# Main.net
KiCad netlist of a schematic drawn in Altium Designer
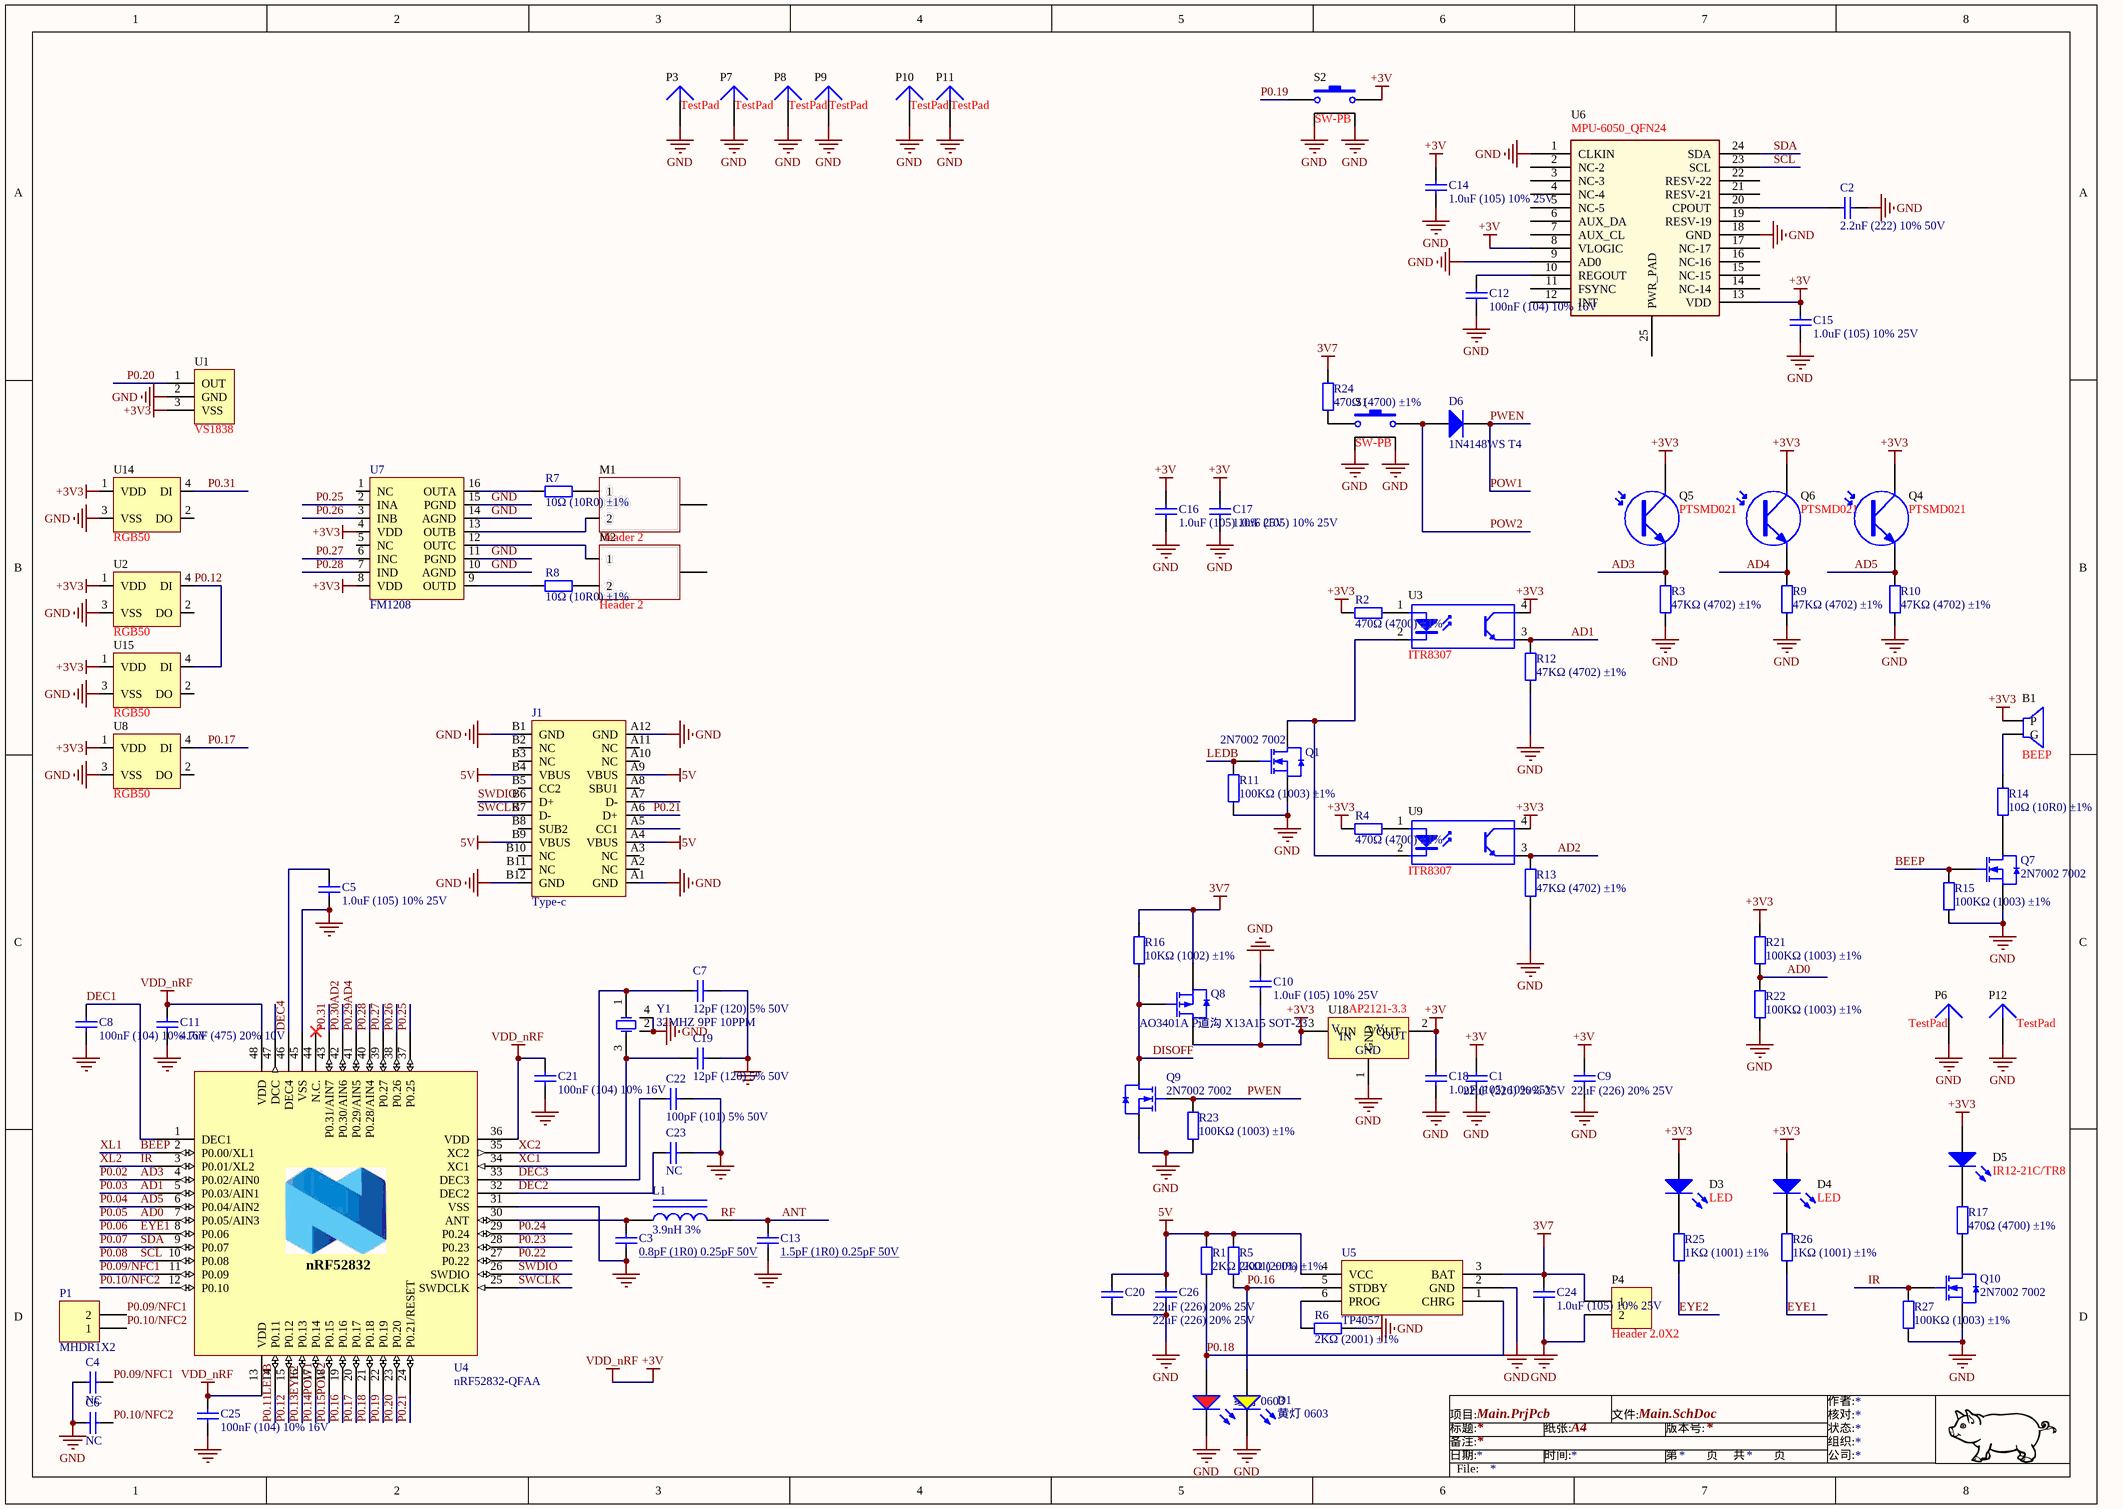
[diagram p0: Main.SchDoc]

(export (version "E")
  (design (tool "Eeschema 10.0.6"))
  (components
    (comp (ref "B1")
      (value "BEEP")
      (footprint "BEEP")
      (description "最小蜂鸣器6MM 6038 6035电磁式蜂鸣器 6*3.5 6*3.8MM 无源 交流")
      (libsource (lib "WARSHIP_SCH") (part "BEEP"))
    )
    (comp (ref "C1")
      (value "22uF (226) 20% 25V")
      (footprint "0805_C")
      (description "贴片电容")
      (libsource (lib "Miscellaneous Devices LC") (part "0805 22uF (226) 20% 25V"))
    )
    (comp (ref "C2")
      (value "2.2nF (222) 10% 50V")
      (footprint "0402_C")
      (description "贴片电容")
      (libsource (lib "Miscellaneous Devices LC") (part "0402 2.2nF (222) 10% 50V"))
    )
    (comp (ref "C3")
      (value "0.8pF (1R0) 0.25pF 50V")
      (footprint "0402_C")
      (description "贴片电容")
      (libsource (lib "Miscellaneous Devices LC") (part "0402 1pF (1R0) 0.25pF 50V"))
    )
    (comp (ref "C4")
      (value "NC")
      (footprint "0402_C")
      (description "贴片电容")
      (libsource (lib "LC") (part "0402 1nF (102) 10% 50V"))
    )
    (comp (ref "C5")
      (value "1.0uF (105) 10% 25V")
      (footprint "0402_C")
      (description "贴片电容")
      (libsource (lib "Miscellaneous Devices LC") (part "0402 1.0uF (105) 10% 25V"))
    )
    (comp (ref "C6")
      (value "NC")
      (footprint "0402_C")
      (description "贴片电容")
      (libsource (lib "LC") (part "0402 1nF (102) 10% 50V"))
    )
    (comp (ref "C7")
      (value "12pF (120) 5% 50V")
      (footprint "0402_C")
      (description "贴片电容")
      (libsource (lib "Miscellaneous Devices LC") (part "0402 12pF (120) 5% 50V"))
    )
    (comp (ref "C8")
      (value "100nF (104) 10% 16V")
      (footprint "0402_C")
      (description "贴片电容")
      (libsource (lib "Miscellaneous Devices LC") (part "0402 100nF (104) 10% 16V"))
    )
    (comp (ref "C9")
      (value "22uF (226) 20% 25V")
      (footprint "0805_C")
      (description "贴片电容")
      (libsource (lib "Miscellaneous Devices LC") (part "0805 22uF (226) 20% 25V"))
    )
    (comp (ref "C10")
      (value "1.0uF (105) 10% 25V")
      (footprint "0402_C")
      (description "贴片电容")
      (libsource (lib "Miscellaneous Devices LC") (part "0402 1.0uF (105) 10% 25V"))
    )
    (comp (ref "C11")
      (value "4.7uF (475) 20% 10V")
      (footprint "0402_C")
      (description "贴片电容")
      (libsource (lib "Miscellaneous Devices LC") (part "0402 4.7uF (475) 20% 10V"))
    )
    (comp (ref "C12")
      (value "100nF (104) 10% 16V")
      (footprint "0402_C")
      (description "贴片电容")
      (libsource (lib "Miscellaneous Devices LC") (part "0402 100nF (104) 10% 16V"))
    )
    (comp (ref "C13")
      (value "1.5pF (1R0) 0.25pF 50V")
      (footprint "0402_C")
      (description "贴片电容")
      (libsource (lib "Miscellaneous Devices LC") (part "0402 1pF (1R0) 0.25pF 50V"))
    )
    (comp (ref "C14")
      (value "1.0uF (105) 10% 25V")
      (footprint "0402_C")
      (description "贴片电容")
      (libsource (lib "Miscellaneous Devices LC") (part "0402 1.0uF (105) 10% 25V"))
    )
    (comp (ref "C15")
      (value "1.0uF (105) 10% 25V")
      (footprint "0402_C")
      (description "贴片电容")
      (libsource (lib "Miscellaneous Devices LC") (part "0402 1.0uF (105) 10% 25V"))
    )
    (comp (ref "C16")
      (value "1.0uF (105) 10% 25V")
      (footprint "0402_C")
      (description "贴片电容")
      (libsource (lib "Miscellaneous Devices LC") (part "0402 1.0uF (105) 10% 25V"))
    )
    (comp (ref "C17")
      (value "1.0uF (105) 10% 25V")
      (footprint "0402_C")
      (description "贴片电容")
      (libsource (lib "Miscellaneous Devices LC") (part "0402 1.0uF (105) 10% 25V"))
    )
    (comp (ref "C18")
      (value "1.0uF (105) 10% 25V")
      (footprint "0402_C")
      (description "贴片电容")
      (libsource (lib "Miscellaneous Devices LC") (part "0402 1.0uF (105) 10% 25V"))
    )
    (comp (ref "C19")
      (value "12pF (120) 5% 50V")
      (footprint "0402_C")
      (description "贴片电容")
      (libsource (lib "Miscellaneous Devices LC") (part "0402 12pF (120) 5% 50V"))
    )
    (comp (ref "C20")
      (value "22uF (226) 20% 25V")
      (footprint "0805_C")
      (description "贴片电容")
      (libsource (lib "Miscellaneous Devices LC") (part "0805 22uF (226) 20% 25V"))
    )
    (comp (ref "C21")
      (value "100nF (104) 10% 16V")
      (footprint "0402_C")
      (description "贴片电容")
      (libsource (lib "Miscellaneous Devices LC") (part "0402 100nF (104) 10% 16V"))
    )
    (comp (ref "C22")
      (value "100pF (101) 5% 50V")
      (footprint "0402_C")
      (description "贴片电容")
      (libsource (lib "Miscellaneous Devices LC") (part "0402 100pF (101) 5% 50V"))
    )
    (comp (ref "C23")
      (value "NC")
      (footprint "0402_C")
      (description "贴片电容")
      (libsource (lib "Miscellaneous Devices LC") (part "0402 100pF (101) 5% 50V"))
    )
    (comp (ref "C24")
      (value "1.0uF (105) 10% 25V")
      (footprint "0402_C")
      (description "贴片电容")
      (libsource (lib "Miscellaneous Devices LC") (part "0402 1.0uF (105) 10% 25V"))
    )
    (comp (ref "C25")
      (value "100nF (104) 10% 16V")
      (footprint "0402_C")
      (description "贴片电容")
      (libsource (lib "Miscellaneous Devices LC") (part "0402 100nF (104) 10% 16V"))
    )
    (comp (ref "C26")
      (value "22uF (226) 20% 25V")
      (footprint "0805_C")
      (description "贴片电容")
      (libsource (lib "Miscellaneous Devices LC") (part "0805 22uF (226) 20% 25V"))
    )
    (comp (ref "D1")
      (value "黄灯 0603")
      (footprint "0603_LED_S1")
      (description "发光二极管")
      (libsource (lib "Miscellaneous Devices LC") (part "0603 黄灯"))
    )
    (comp (ref "D2")
      (value "红灯 0603")
      (footprint "0603_LED_S1")
      (description "发光二极管")
      (libsource (lib "Miscellaneous Devices LC") (part "0603 红灯"))
    )
    (comp (ref "D3")
      (value "LED")
      (footprint "0802")
      (description "Typical RED, GREEN, YELLOW, AMBER GaAs LED")
      (fields (field (name "PUBLISHER") "Altium Limited"))
      (libsource (lib "Miscellaneous Devices") (part "LED0805"))
    )
    (comp (ref "D4")
      (value "LED")
      (footprint "0802")
      (description "Typical RED, GREEN, YELLOW, AMBER GaAs LED")
      (fields (field (name "PUBLISHER") "Altium Limited"))
      (libsource (lib "Miscellaneous Devices") (part "LED0805"))
    )
    (comp (ref "D5")
      (value "IR12-21C/TR8")
      (footprint "1206")
      (description "侧贴红外发射管")
      (fields (field (name "PUBLISHER") "Altium Limited"))
      (libsource (lib "Miscellaneous Devices") (part "LED0805"))
    )
    (comp (ref "D6")
      (value "1N4148WS T4")
      (footprint "SOD-323")
      (description "二极管")
      (libsource (lib "Miscellaneous Devices LC") (part "SOD-323 1N4148WS T4"))
    )
    (comp (ref "J1") (value "Type-c") (footprint "Type-c") (libsource (lib "Main") (part "Type-c")))
    (comp (ref "L1")
      (value "3.9nH 3%")
      (footprint "0402_L")
      (description "贴片电感")
      (libsource (lib "Miscellaneous Devices LC") (part "0402 3.9nH 3%"))
    )
    (comp (ref "M1")
      (value "Header 2")
      (footprint "PAD2")
      (description "Header, 2-Pin")
      (fields (field (name "PUBLISHER") "Altium Limited"))
      (libsource (lib "甲壳虫Geek-InSect_1") (part "Header 2"))
    )
    (comp (ref "M2")
      (value "Header 2")
      (footprint "PAD2")
      (description "Header, 2-Pin")
      (fields (field (name "PUBLISHER") "Altium Limited"))
      (libsource (lib "甲壳虫Geek-InSect_1") (part "Header 2"))
    )
    (comp (ref "P1")
      (value "MHDR1X2")
      (footprint "MHDR1X2")
      (description "Header, 2-Pin")
      (fields (field (name "PUBLISHER") "Altium Limited"))
      (libsource (lib "Miscellaneous Connectors") (part "MHDR1X2"))
    )
    (comp (ref "P3")
      (value "TestPad")
      (footprint "MOTO")
      (description "Plug")
      (fields (field (name "PUBLISHER") "Altium Limited"))
      (libsource (lib "Miscellaneous Connectors") (part "Plug"))
    )
    (comp (ref "P4")
      (value "Header 2.0X2")
      (footprint "Head2.0")
      (description "2.0dip连接器")
      (fields (field (name "PUBLISHER") "Altium Limited"))
      (libsource (lib "Miscellaneous Connectors") (part "Header 2"))
    )
    (comp (ref "P6")
      (value "TestPad")
      (footprint "PAD")
      (description "Plug")
      (fields (field (name "PUBLISHER") "Altium Limited"))
      (libsource (lib "Miscellaneous Connectors") (part "Plug"))
    )
    (comp (ref "P7")
      (value "TestPad")
      (footprint "MOTO")
      (description "Plug")
      (fields (field (name "PUBLISHER") "Altium Limited"))
      (libsource (lib "Miscellaneous Connectors") (part "Plug"))
    )
    (comp (ref "P8")
      (value "TestPad")
      (footprint "PAD")
      (description "Plug")
      (fields (field (name "PUBLISHER") "Altium Limited"))
      (libsource (lib "Miscellaneous Connectors") (part "Plug"))
    )
    (comp (ref "P9")
      (value "TestPad")
      (footprint "PAD")
      (description "Plug")
      (fields (field (name "PUBLISHER") "Altium Limited"))
      (libsource (lib "Miscellaneous Connectors") (part "Plug"))
    )
    (comp (ref "P10")
      (value "TestPad")
      (footprint "PAD")
      (description "Plug")
      (fields (field (name "PUBLISHER") "Altium Limited"))
      (libsource (lib "Miscellaneous Connectors") (part "Plug"))
    )
    (comp (ref "P11")
      (value "TestPad")
      (footprint "PAD")
      (description "Plug")
      (fields (field (name "PUBLISHER") "Altium Limited"))
      (libsource (lib "Miscellaneous Connectors") (part "Plug"))
    )
    (comp (ref "P12")
      (value "TestPad")
      (footprint "PAD")
      (description "Plug")
      (fields (field (name "PUBLISHER") "Altium Limited"))
      (libsource (lib "Miscellaneous Connectors") (part "Plug"))
    )
    (comp (ref "Q1")
      (value "2N7002 7002")
      (footprint "SOT-23")
      (description "MOS(场效应管)")
      (libsource (lib "Miscellaneous Devices LC") (part "2N7002 7002"))
    )
    (comp (ref "Q4")
      (value "PTSMD021")
      (footprint "EYE")
      (description "光线传感器")
      (fields (field (name "PUBLISHER") "Altium Limited"))
      (libsource (lib "Miscellaneous Devices") (part "Photo NPN"))
    )
    (comp (ref "Q5")
      (value "PTSMD021")
      (footprint "EYE")
      (description "光线传感器")
      (fields (field (name "PUBLISHER") "Altium Limited"))
      (libsource (lib "Miscellaneous Devices") (part "Photo NPN"))
    )
    (comp (ref "Q6")
      (value "PTSMD021")
      (footprint "EYE")
      (description "光线传感器")
      (fields (field (name "PUBLISHER") "Altium Limited"))
      (libsource (lib "Miscellaneous Devices") (part "Photo NPN"))
    )
    (comp (ref "Q7")
      (value "2N7002 7002")
      (footprint "SOT-23")
      (description "MOS(场效应管)")
      (libsource (lib "Miscellaneous Devices LC") (part "2N7002 7002"))
    )
    (comp (ref "Q8")
      (value "AO3401A P道沟 X13A15 SOT-23")
      (footprint "SOT-23-3L")
      (description "MOS(场效应管)")
      (libsource (lib "Miscellaneous Devices LC") (part "AO3401A P道沟 X13A15 SOT-23"))
    )
    (comp (ref "Q9")
      (value "2N7002 7002")
      (footprint "SOT-23")
      (description "MOS(场效应管)")
      (libsource (lib "Miscellaneous Devices LC") (part "2N7002 7002"))
    )
    (comp (ref "Q10")
      (value "2N7002 7002")
      (footprint "SOT-23")
      (description "MOS(场效应管)")
      (libsource (lib "Miscellaneous Devices LC") (part "2N7002 7002"))
    )
    (comp (ref "R1")
      (value "2KΩ (2001) ±1%")
      (footprint "0402_R")
      (description "贴片电阻")
      (libsource (lib "Miscellaneous Devices LC") (part "0402 2KΩ (2001) 1%"))
    )
    (comp (ref "R2")
      (value "470Ω (4700) ±1%")
      (footprint "0402_R")
      (description "贴片电阻")
      (libsource (lib "Miscellaneous Devices LC") (part "0402 470Ω (4700) 1%"))
    )
    (comp (ref "R3")
      (value "47KΩ (4702) ±1%")
      (footprint "0402_R")
      (description "贴片电阻")
      (libsource (lib "Miscellaneous Devices LC") (part "0402 47KΩ (4702) 1%"))
    )
    (comp (ref "R4")
      (value "470Ω (4700) ±1%")
      (footprint "0402_R")
      (description "贴片电阻")
      (libsource (lib "Miscellaneous Devices LC") (part "0402 470Ω (4700) 1%"))
    )
    (comp (ref "R5")
      (value "2KΩ (2001) ±1%")
      (footprint "0402_R")
      (description "贴片电阻")
      (libsource (lib "Miscellaneous Devices LC") (part "0402 2KΩ (2001) 1%"))
    )
    (comp (ref "R6")
      (value "2KΩ (2001) ±1%")
      (footprint "0402_R")
      (description "贴片电阻")
      (libsource (lib "") (part "0402 2KΩ (2001) 1%_1"))
    )
    (comp (ref "R7")
      (value "10Ω (10R0) ±1%")
      (footprint "0603_R")
      (description "贴片电阻")
      (libsource (lib "Miscellaneous Devices LC") (part "0603 10Ω (10R0) 1%"))
    )
    (comp (ref "R8")
      (value "10Ω (10R0) ±1%")
      (footprint "0603_R")
      (description "贴片电阻")
      (libsource (lib "Miscellaneous Devices LC") (part "0603 10Ω (10R0) 1%"))
    )
    (comp (ref "R9")
      (value "47KΩ (4702) ±1%")
      (footprint "0402_R")
      (description "贴片电阻")
      (libsource (lib "Miscellaneous Devices LC") (part "0402 47KΩ (4702) 1%"))
    )
    (comp (ref "R10")
      (value "47KΩ (4702) ±1%")
      (footprint "0402_R")
      (description "贴片电阻")
      (libsource (lib "Miscellaneous Devices LC") (part "0402 47KΩ (4702) 1%"))
    )
    (comp (ref "R11")
      (value "100KΩ (1003) ±1%")
      (footprint "0402_R")
      (description "贴片电阻")
      (libsource (lib "Miscellaneous Devices LC") (part "0402 100KΩ (1003) 1%"))
    )
    (comp (ref "R12")
      (value "47KΩ (4702) ±1%")
      (footprint "0402_R")
      (description "贴片电阻")
      (libsource (lib "Miscellaneous Devices LC") (part "0402 47KΩ (4702) 1%"))
    )
    (comp (ref "R13")
      (value "47KΩ (4702) ±1%")
      (footprint "0402_R")
      (description "贴片电阻")
      (libsource (lib "Miscellaneous Devices LC") (part "0402 47KΩ (4702) 1%"))
    )
    (comp (ref "R14")
      (value "10Ω (10R0) ±1%")
      (footprint "0402_R")
      (description "贴片电阻")
      (libsource (lib "Miscellaneous Devices LC") (part "0402 10Ω (10R0) 1%"))
    )
    (comp (ref "R15")
      (value "100KΩ (1003) ±1%")
      (footprint "0402_R")
      (description "贴片电阻")
      (libsource (lib "Miscellaneous Devices LC") (part "0402 100KΩ (1003) 1%"))
    )
    (comp (ref "R16")
      (value "10KΩ (1002) ±1%")
      (footprint "0402_R")
      (description "贴片电阻")
      (libsource (lib "Miscellaneous Devices LC") (part "0402 10KΩ (1002) 1%"))
    )
    (comp (ref "R17")
      (value "470Ω (4700) ±1%")
      (footprint "0402_R")
      (description "贴片电阻")
      (libsource (lib "") (part "0402 470Ω (4700) 1%_1"))
    )
    (comp (ref "R21")
      (value "100KΩ (1003) ±1%")
      (footprint "0402_R")
      (description "贴片电阻")
      (libsource (lib "Miscellaneous Devices LC") (part "0402 100KΩ (1003) 1%"))
    )
    (comp (ref "R22")
      (value "100KΩ (1003) ±1%")
      (footprint "0402_R")
      (description "贴片电阻")
      (libsource (lib "Miscellaneous Devices LC") (part "0402 100KΩ (1003) 1%"))
    )
    (comp (ref "R23")
      (value "100KΩ (1003) ±1%")
      (footprint "0402_R")
      (description "贴片电阻")
      (libsource (lib "Miscellaneous Devices LC") (part "0402 100KΩ (1003) 1%"))
    )
    (comp (ref "R24")
      (value "470Ω (4700) ±1%")
      (footprint "0402_R")
      (description "贴片电阻")
      (libsource (lib "") (part "0402 470Ω (4700) 1%_1"))
    )
    (comp (ref "R25")
      (value "1KΩ (1001) ±1%")
      (footprint "0402_R")
      (description "贴片电阻")
      (libsource (lib "Miscellaneous Devices LC") (part "0402 1KΩ (1001) 1%"))
    )
    (comp (ref "R26")
      (value "1KΩ (1001) ±1%")
      (footprint "0402_R")
      (description "贴片电阻")
      (libsource (lib "Miscellaneous Devices LC") (part "0402 1KΩ (1001) 1%"))
    )
    (comp (ref "R27")
      (value "100KΩ (1003) ±1%")
      (footprint "0402_R")
      (description "贴片电阻")
      (libsource (lib "Miscellaneous Devices LC") (part "0402 100KΩ (1003) 1%"))
    )
    (comp (ref "S1")
      (value "SW-PB")
      (footprint "BUTTON")
      (description "3x6x3.5H 3*6*3.5贴片 侧位 按钮")
      (fields (field (name "PUBLISHER") "Altium Limited"))
      (libsource (lib "甲壳虫Geek-InSect_1") (part "SW-PB"))
    )
    (comp (ref "S2")
      (value "SW-PB")
      (footprint "BUTTON")
      (description "3x6x3.5H 3*6*3.5贴片 侧位 按钮")
      (fields (field (name "PUBLISHER") "Altium Limited"))
      (libsource (lib "甲壳虫Geek-InSect_1") (part "SW-PB"))
    )
    (comp (ref "U1")
      (value "VS1838")
      (footprint "IR38")
      (description "1838 接收头 VS1838 VS1838B")
      (libsource (lib "甲壳虫Geek-InSect_1") (part "RF"))
    )
    (comp (ref "U2")
      (value "RGB50")
      (footprint "HV-EYE - duplicate")
      (description "全彩REG灯珠PCB附件")
      (libsource (lib "甲壳虫Geek-InSect") (part "RGB50"))
    )
    (comp (ref "U3")
      (value "ITR8307")
      (footprint "ITR8307")
      (description "反射式光学传感器")
      (fields (field (name "PUBLISHER") "Altium Limited"))
      (libsource (lib "甲壳虫Geek-InSect") (part "Optoisolator1"))
    )
    (comp (ref "U4")
      (value "nRF52832-QFAA")
      (footprint "QFN40P600X600X90-48N")
      (description "Multi-protocol Bluetooth Low Energy and 2.4GHz proprietary system-on-chip")
      (fields
        (field (name "MANUFACTURER") "Nordic Semiconductor")
        (field (name "PUBLISHER") "Nordic Semiconductor")
      )
      (libsource (lib "Nordic Active DB") (part "nRF52832_QFAA"))
    )
    (comp (ref "U5")
      (value "TP4057")
      (footprint "SOT23-6_N")
      (description "电池电源管理")
      (libsource (lib "Miscellaneous Devices LC") (part "TP4057"))
    )
    (comp (ref "U6")
      (value "MPU-6050_QFN24")
      (footprint "qfn24")
      (description "三轴陀螺仪加速度")
      (libsource (lib "*") (part "MPU06050_QFN24"))
    )
    (comp (ref "U7") (value "FM1208") (footprint "SO-16_L") (libsource (lib "Main") (part "FM1208S")))
    (comp (ref "U8")
      (value "RGB50")
      (footprint "WS2812")
      (description "WS2812全彩RGB灯珠")
      (libsource (lib "甲壳虫Geek-InSect") (part "RGB50"))
    )
    (comp (ref "U9")
      (value "ITR8307")
      (footprint "ITR8307")
      (description "反射式光学传感器")
      (fields (field (name "PUBLISHER") "Altium Limited"))
      (libsource (lib "甲壳虫Geek-InSect") (part "Optoisolator1"))
    )
    (comp (ref "U14")
      (value "RGB50")
      (footprint "WS2812")
      (description "WS2812全彩RGB灯珠")
      (libsource (lib "甲壳虫Geek-InSect") (part "RGB50"))
    )
    (comp (ref "U15")
      (value "RGB50")
      (footprint "HV-EYE - duplicate")
      (description "全彩REG灯珠PCB附件")
      (libsource (lib "甲壳虫Geek-InSect") (part "RGB50"))
    )
    (comp (ref "U18")
      (value "AP2121-3.3")
      (footprint "SOT-23")
      (description "3V LDO")
      (libsource (lib "wllibs") (part "AP2121-3"))
    )
    (comp (ref "Y1")
      (value "32MHZ 9PF 10PPM")
      (footprint "SMD-3225_4P")
      (description "贴片晶振")
      (libsource (lib "MiniCar") (part "SMD-3225_4P  16MHZ 9PF 10PPM"))
    )
  )
  (nets
    (net (code "1") (name "+3V") (class "Default")
      (node (ref "C1") (pin "2") (pinfunction "2_2") (pintype "passive"))
      (node (ref "C11") (pin "2") (pinfunction "2_2") (pintype "passive"))
      (node (ref "C14") (pin "2") (pinfunction "2_2") (pintype "passive"))
      (node (ref "C15") (pin "2") (pinfunction "2_2") (pintype "passive"))
      (node (ref "C16") (pin "2") (pinfunction "2_2") (pintype "passive"))
      (node (ref "C17") (pin "2") (pinfunction "2_2") (pintype "passive"))
      (node (ref "C18") (pin "2") (pinfunction "2_2") (pintype "passive"))
      (node (ref "C21") (pin "2") (pinfunction "2_2") (pintype "passive"))
      (node (ref "C25") (pin "2") (pinfunction "2_2") (pintype "passive"))
      (node (ref "C9") (pin "2") (pinfunction "2_2") (pintype "passive"))
      (node (ref "S2") (pin "1") (pinfunction "1_1") (pintype "passive"))
      (node (ref "U18") (pin "2") (pinfunction "VOUT_2") (pintype "passive"))
      (node (ref "U4") (pin "13") (pinfunction "VDD_13") (pintype "power_in"))
      (node (ref "U4") (pin "36") (pinfunction "VDD_36") (pintype "power_in"))
      (node (ref "U4") (pin "48") (pinfunction "VDD_48") (pintype "power_in"))
      (node (ref "U6") (pin "13") (pinfunction "VDD_13") (pintype "passive"))
      (node (ref "U6") (pin "8") (pinfunction "VLOGIC_8") (pintype "passive"))
    )
    (net (code "2") (name "+3V3") (class "Default")
      (node (ref "B1") (pin "1") (pinfunction "P_1") (pintype "passive"))
      (node (ref "C10") (pin "1") (pinfunction "1_1") (pintype "passive"))
      (node (ref "D3") (pin "1") (pinfunction "A_1") (pintype "passive"))
      (node (ref "D4") (pin "1") (pinfunction "A_1") (pintype "passive"))
      (node (ref "D5") (pin "1") (pinfunction "A_1") (pintype "passive"))
      (node (ref "Q4") (pin "1") (pinfunction "C_1") (pintype "passive"))
      (node (ref "Q5") (pin "1") (pinfunction "C_1") (pintype "passive"))
      (node (ref "Q6") (pin "1") (pinfunction "C_1") (pintype "passive"))
      (node (ref "Q8") (pin "3") (pinfunction "D_3") (pintype "passive"))
      (node (ref "R2") (pin "1") (pinfunction "1_1") (pintype "passive"))
      (node (ref "R21") (pin "2") (pinfunction "2_2") (pintype "passive"))
      (node (ref "R4") (pin "1") (pinfunction "1_1") (pintype "passive"))
      (node (ref "U1") (pin "3") (pinfunction "VSS_3") (pintype "passive"))
      (node (ref "U14") (pin "1") (pinfunction "VDD_1") (pintype "passive"))
      (node (ref "U15") (pin "1") (pinfunction "VDD_1") (pintype "passive"))
      (node (ref "U18") (pin "3") (pinfunction "VIN_3") (pintype "passive"))
      (node (ref "U2") (pin "1") (pinfunction "VDD_1") (pintype "passive"))
      (node (ref "U3") (pin "4") (pinfunction "C_4") (pintype "passive"))
      (node (ref "U7") (pin "4") (pinfunction "VDD_4") (pintype "passive"))
      (node (ref "U7") (pin "8") (pinfunction "VDD_8") (pintype "passive"))
      (node (ref "U8") (pin "1") (pinfunction "VDD_1") (pintype "passive"))
      (node (ref "U9") (pin "4") (pinfunction "C_4") (pintype "passive"))
    )
    (net (code "3") (name "/AD0") (class "Default")
      (node (ref "R21") (pin "1") (pinfunction "1_1") (pintype "passive"))
      (node (ref "R22") (pin "2") (pinfunction "2_2") (pintype "passive"))
      (node (ref "U4") (pin "7") (pinfunction "P0.05/AIN3_7") (pintype "bidirectional"))
    )
    (net (code "4") (name "/AD1") (class "Default")
      (node (ref "R12") (pin "2") (pinfunction "2_2") (pintype "passive"))
      (node (ref "U3") (pin "3") (pinfunction "E_3") (pintype "passive"))
      (node (ref "U4") (pin "5") (pinfunction "P0.03/AIN1_5") (pintype "bidirectional"))
    )
    (net (code "5") (name "/AD2") (class "Default")
      (node (ref "R13") (pin "2") (pinfunction "2_2") (pintype "passive"))
      (node (ref "U4") (pin "42") (pinfunction "P0.30/AIN6_42") (pintype "bidirectional"))
      (node (ref "U9") (pin "3") (pinfunction "E_3") (pintype "passive"))
    )
    (net (code "6") (name "/AD3") (class "Default")
      (node (ref "Q5") (pin "2") (pinfunction "E_2") (pintype "passive"))
      (node (ref "R3") (pin "2") (pinfunction "2_2") (pintype "passive"))
      (node (ref "U4") (pin "4") (pinfunction "P0.02/AIN0_4") (pintype "bidirectional"))
    )
    (net (code "7") (name "/AD4") (class "Default")
      (node (ref "Q6") (pin "2") (pinfunction "E_2") (pintype "passive"))
      (node (ref "R9") (pin "2") (pinfunction "2_2") (pintype "passive"))
      (node (ref "U4") (pin "41") (pinfunction "P0.29/AIN5_41") (pintype "bidirectional"))
    )
    (net (code "8") (name "/AD5") (class "Default")
      (node (ref "Q4") (pin "2") (pinfunction "E_2") (pintype "passive"))
      (node (ref "R10") (pin "2") (pinfunction "2_2") (pintype "passive"))
      (node (ref "U4") (pin "6") (pinfunction "P0.04/AIN2_6") (pintype "bidirectional"))
    )
    (net (code "9") (name "/ANT") (class "Default")
      (node (ref "C13") (pin "2") (pinfunction "2_2") (pintype "passive"))
      (node (ref "L1") (pin "2") (pinfunction "2_2") (pintype "passive"))
    )
    (net (code "10") (name "/BEEP") (class "Default")
      (node (ref "Q7") (pin "1") (pinfunction "G_1") (pintype "passive"))
      (node (ref "R15") (pin "2") (pinfunction "2_2") (pintype "passive"))
      (node (ref "U4") (pin "2") (pinfunction "P0.00/XL1_2") (pintype "bidirectional"))
    )
    (net (code "11") (name "/DEC1") (class "Default")
      (node (ref "C8") (pin "2") (pinfunction "2_2") (pintype "passive"))
      (node (ref "U4") (pin "1") (pinfunction "DEC1_1") (pintype "power_in"))
    )
    (net (code "12") (name "/DEC2") (class "Default")
      (node (ref "C23") (pin "1") (pinfunction "1_1") (pintype "passive"))
      (node (ref "U4") (pin "32") (pinfunction "DEC2_32") (pintype "power_in"))
    )
    (net (code "13") (name "/DEC3") (class "Default")
      (node (ref "C22") (pin "1") (pinfunction "1_1") (pintype "passive"))
      (node (ref "U4") (pin "33") (pinfunction "DEC3_33") (pintype "power_in"))
    )
    (net (code "14") (name "/DEC4") (class "Default")
      (node (ref "C5") (pin "2") (pinfunction "2_2") (pintype "passive"))
      (node (ref "U4") (pin "46") (pinfunction "DEC4_46") (pintype "power_in"))
    )
    (net (code "15") (name "/DISOFF") (class "Default")
      (node (ref "Q8") (pin "1") (pinfunction "G_1") (pintype "passive"))
      (node (ref "Q9") (pin "3") (pinfunction "D_3") (pintype "passive"))
      (node (ref "R16") (pin "1") (pinfunction "1_1") (pintype "passive"))
    )
    (net (code "16") (name "/EYE1") (class "Default")
      (node (ref "R26") (pin "1") (pinfunction "1_1") (pintype "passive"))
      (node (ref "U4") (pin "8") (pinfunction "P0.06_8") (pintype "bidirectional"))
    )
    (net (code "17") (name "/EYE2") (class "Default")
      (node (ref "R25") (pin "1") (pinfunction "1_1") (pintype "passive"))
      (node (ref "U4") (pin "16") (pinfunction "P0.13_16") (pintype "bidirectional"))
    )
    (net (code "18") (name "/IR") (class "Default")
      (node (ref "Q10") (pin "1") (pinfunction "G_1") (pintype "passive"))
      (node (ref "R27") (pin "2") (pinfunction "2_2") (pintype "passive"))
      (node (ref "U4") (pin "3") (pinfunction "P0.01/XL2_3") (pintype "bidirectional"))
    )
    (net (code "19") (name "/LEDB") (class "Default")
      (node (ref "Q1") (pin "1") (pinfunction "G_1") (pintype "passive"))
      (node (ref "R11") (pin "2") (pinfunction "2_2") (pintype "passive"))
      (node (ref "U4") (pin "14") (pinfunction "P0.11_14") (pintype "bidirectional"))
    )
    (net (code "20") (name "/P0.07") (class "Default")
      (node (ref "U4") (pin "9") (pinfunction "P0.07_9") (pintype "bidirectional"))
      (node (ref "U6") (pin "24") (pinfunction "SDA_24") (pintype "passive"))
    )
    (net (code "21") (name "/P0.08") (class "Default")
      (node (ref "U4") (pin "10") (pinfunction "P0.08_10") (pintype "bidirectional"))
      (node (ref "U6") (pin "23") (pinfunction "SCL_23") (pintype "passive"))
    )
    (net (code "22") (name "/P0.09{slash}NFC1") (class "Default")
      (node (ref "C4") (pin "1") (pinfunction "1_1") (pintype "passive"))
      (node (ref "P1") (pin "2") (pinfunction "2_2") (pintype "passive"))
      (node (ref "U4") (pin "11") (pinfunction "P0.09_11") (pintype "bidirectional"))
    )
    (net (code "23") (name "/P0.10{slash}NFC2") (class "Default")
      (node (ref "C6") (pin "2") (pinfunction "2_2") (pintype "passive"))
      (node (ref "P1") (pin "1") (pinfunction "1_1") (pintype "passive"))
      (node (ref "U4") (pin "12") (pinfunction "P0.10_12") (pintype "bidirectional"))
    )
    (net (code "24") (name "/P0.12") (class "Default")
      (node (ref "U15") (pin "4") (pinfunction "DI_4") (pintype "passive"))
      (node (ref "U2") (pin "4") (pinfunction "DI_4") (pintype "passive"))
      (node (ref "U4") (pin "15") (pinfunction "P0.12_15") (pintype "bidirectional"))
    )
    (net (code "25") (name "/P0.14") (class "Default")
      (node (ref "D6") (pin "2") (pinfunction "K_2") (pintype "passive"))
      (node (ref "Q9") (pin "1") (pinfunction "G_1") (pintype "passive"))
      (node (ref "R23") (pin "2") (pinfunction "2_2") (pintype "passive"))
      (node (ref "U4") (pin "17") (pinfunction "P0.14_17") (pintype "bidirectional"))
    )
    (net (code "26") (name "/P0.15") (class "Default")
      (node (ref "D6") (pin "1") (pinfunction "A_1") (pintype "passive"))
      (node (ref "S1") (pin "2") (pinfunction "2_2") (pintype "passive"))
      (node (ref "U4") (pin "18") (pinfunction "P0.15_18") (pintype "bidirectional"))
    )
    (net (code "27") (name "/P0.16") (class "Default")
      (node (ref "D1") (pin "A") (pinfunction "A_A") (pintype "passive"))
      (node (ref "R5") (pin "1") (pinfunction "1_1") (pintype "passive"))
      (node (ref "U4") (pin "19") (pinfunction "P0.16_19") (pintype "bidirectional"))
      (node (ref "U5") (pin "5") (pinfunction "STDBY_5") (pintype "passive"))
    )
    (net (code "28") (name "/P0.17") (class "Default")
      (node (ref "U4") (pin "20") (pinfunction "P0.17_20") (pintype "bidirectional"))
      (node (ref "U8") (pin "4") (pinfunction "DI_4") (pintype "passive"))
    )
    (net (code "29") (name "/P0.18") (class "Default")
      (node (ref "D2") (pin "A") (pinfunction "A_A") (pintype "passive"))
      (node (ref "R1") (pin "1") (pinfunction "1_1") (pintype "passive"))
      (node (ref "U4") (pin "21") (pinfunction "P0.18_21") (pintype "bidirectional"))
      (node (ref "U5") (pin "1") (pinfunction "CHRG_1") (pintype "passive"))
    )
    (net (code "30") (name "/P0.19") (class "Default")
      (node (ref "S2") (pin "2") (pinfunction "2_2") (pintype "passive"))
      (node (ref "U4") (pin "22") (pinfunction "P0.19_22") (pintype "bidirectional"))
    )
    (net (code "31") (name "/P0.20") (class "Default")
      (node (ref "U1") (pin "1") (pinfunction "OUT_1") (pintype "passive"))
      (node (ref "U4") (pin "23") (pinfunction "P0.20_23") (pintype "bidirectional"))
    )
    (net (code "32") (name "/P0.21") (class "Default")
      (node (ref "J1") (pin "A6") (pinfunction "D+_A6") (pintype "passive"))
      (node (ref "U4") (pin "24") (pinfunction "P0.21/RESET_24") (pintype "bidirectional"))
    )
    (net (code "33") (name "/P0.22") (class "Default")
      (node (ref "U4") (pin "27") (pinfunction "P0.22_27") (pintype "bidirectional"))
    )
    (net (code "34") (name "/P0.23") (class "Default")
      (node (ref "U4") (pin "28") (pinfunction "P0.23_28") (pintype "bidirectional"))
    )
    (net (code "35") (name "/P0.24") (class "Default")
      (node (ref "U4") (pin "29") (pinfunction "P0.24_29") (pintype "bidirectional"))
    )
    (net (code "36") (name "/P0.25") (class "Default")
      (node (ref "U4") (pin "37") (pinfunction "P0.25_37") (pintype "bidirectional"))
      (node (ref "U7") (pin "2") (pinfunction "INA_2") (pintype "passive"))
    )
    (net (code "37") (name "/P0.26") (class "Default")
      (node (ref "U4") (pin "38") (pinfunction "P0.26_38") (pintype "bidirectional"))
      (node (ref "U7") (pin "3") (pinfunction "INB_3") (pintype "passive"))
    )
    (net (code "38") (name "/P0.27") (class "Default")
      (node (ref "U4") (pin "39") (pinfunction "P0.27_39") (pintype "bidirectional"))
      (node (ref "U7") (pin "6") (pinfunction "INC_6") (pintype "passive"))
    )
    (net (code "39") (name "/P0.28") (class "Default")
      (node (ref "U4") (pin "40") (pinfunction "P0.28/AIN4_40") (pintype "bidirectional"))
      (node (ref "U7") (pin "7") (pinfunction "IND_7") (pintype "passive"))
    )
    (net (code "40") (name "/P0.31") (class "Default")
      (node (ref "U14") (pin "4") (pinfunction "DI_4") (pintype "passive"))
      (node (ref "U4") (pin "43") (pinfunction "P0.31/AIN7_43") (pintype "bidirectional"))
    )
    (net (code "42") (name "/SWCLK") (class "Default")
      (node (ref "J1") (pin "B7") (pinfunction "D-_B7") (pintype "passive"))
      (node (ref "U4") (pin "25") (pinfunction "SWDCLK_25") (pintype "input"))
    )
    (net (code "43") (name "/SWDIO") (class "Default")
      (node (ref "J1") (pin "B6") (pinfunction "D+_B6") (pintype "passive"))
      (node (ref "U4") (pin "26") (pinfunction "SWDIO_26") (pintype "bidirectional"))
    )
    (net (code "44") (name "/XC1") (class "Default")
      (node (ref "C19") (pin "1") (pinfunction "1_1") (pintype "passive"))
      (node (ref "U4") (pin "34") (pinfunction "XC1_34") (pintype "input"))
      (node (ref "Y1") (pin "3") (pinfunction "OSC2_3") (pintype "passive"))
    )
    (net (code "45") (name "/XC2") (class "Default")
      (node (ref "C7") (pin "1") (pinfunction "1_1") (pintype "passive"))
      (node (ref "U4") (pin "35") (pinfunction "XC2_35") (pintype "output"))
      (node (ref "Y1") (pin "1") (pinfunction "OSC1_1") (pintype "passive"))
    )
    (net (code "46") (name "3V7") (class "Default")
      (node (ref "C24") (pin "2") (pinfunction "2_2") (pintype "passive"))
      (node (ref "P4") (pin "1") (pinfunction "1_1") (pintype "passive"))
      (node (ref "Q8") (pin "2") (pinfunction "S_2") (pintype "passive"))
      (node (ref "R16") (pin "2") (pinfunction "2_2") (pintype "passive"))
      (node (ref "R24") (pin "2") (pinfunction "2_2") (pintype "passive"))
      (node (ref "U5") (pin "3") (pinfunction "BAT_3") (pintype "passive"))
    )
    (net (code "47") (name "5V") (class "Default")
      (node (ref "C20") (pin "2") (pinfunction "2_2") (pintype "passive"))
      (node (ref "C26") (pin "2") (pinfunction "2_2") (pintype "passive"))
      (node (ref "J1") (pin "A4") (pinfunction "VBUS_A4") (pintype "passive"))
      (node (ref "J1") (pin "A9") (pinfunction "VBUS_A9") (pintype "passive"))
      (node (ref "J1") (pin "B4") (pinfunction "VBUS_B4") (pintype "passive"))
      (node (ref "J1") (pin "B9") (pinfunction "VBUS_B9") (pintype "passive"))
      (node (ref "R1") (pin "2") (pinfunction "2_2") (pintype "passive"))
      (node (ref "R5") (pin "2") (pinfunction "2_2") (pintype "passive"))
      (node (ref "U5") (pin "4") (pinfunction "VCC_4") (pintype "passive"))
    )
    (net (code "48") (name "GND") (class "Default")
      (node (ref "C1") (pin "1") (pinfunction "1_1") (pintype "passive"))
      (node (ref "C10") (pin "2") (pinfunction "2_2") (pintype "passive"))
      (node (ref "C11") (pin "1") (pinfunction "1_1") (pintype "passive"))
      (node (ref "C12") (pin "1") (pinfunction "1_1") (pintype "passive"))
      (node (ref "C13") (pin "1") (pinfunction "1_1") (pintype "passive"))
      (node (ref "C14") (pin "1") (pinfunction "1_1") (pintype "passive"))
      (node (ref "C15") (pin "1") (pinfunction "1_1") (pintype "passive"))
      (node (ref "C16") (pin "1") (pinfunction "1_1") (pintype "passive"))
      (node (ref "C17") (pin "1") (pinfunction "1_1") (pintype "passive"))
      (node (ref "C18") (pin "1") (pinfunction "1_1") (pintype "passive"))
      (node (ref "C19") (pin "2") (pinfunction "2_2") (pintype "passive"))
      (node (ref "C2") (pin "2") (pinfunction "2_2") (pintype "passive"))
      (node (ref "C20") (pin "1") (pinfunction "1_1") (pintype "passive"))
      (node (ref "C21") (pin "1") (pinfunction "1_1") (pintype "passive"))
      (node (ref "C22") (pin "2") (pinfunction "2_2") (pintype "passive"))
      (node (ref "C23") (pin "2") (pinfunction "2_2") (pintype "passive"))
      (node (ref "C24") (pin "1") (pinfunction "1_1") (pintype "passive"))
      (node (ref "C25") (pin "1") (pinfunction "1_1") (pintype "passive"))
      (node (ref "C26") (pin "1") (pinfunction "1_1") (pintype "passive"))
      (node (ref "C3") (pin "1") (pinfunction "1_1") (pintype "passive"))
      (node (ref "C4") (pin "2") (pinfunction "2_2") (pintype "passive"))
      (node (ref "C5") (pin "1") (pinfunction "1_1") (pintype "passive"))
      (node (ref "C6") (pin "1") (pinfunction "1_1") (pintype "passive"))
      (node (ref "C7") (pin "2") (pinfunction "2_2") (pintype "passive"))
      (node (ref "C8") (pin "1") (pinfunction "1_1") (pintype "passive"))
      (node (ref "C9") (pin "1") (pinfunction "1_1") (pintype "passive"))
      (node (ref "D1") (pin "K") (pinfunction "K_K") (pintype "passive"))
      (node (ref "D2") (pin "K") (pinfunction "K_K") (pintype "passive"))
      (node (ref "J1") (pin "A1") (pinfunction "GND_A1") (pintype "passive"))
      (node (ref "J1") (pin "A12") (pinfunction "GND_A12") (pintype "passive"))
      (node (ref "J1") (pin "B1") (pinfunction "GND_B1") (pintype "passive"))
      (node (ref "J1") (pin "B12") (pinfunction "GND_B12") (pintype "passive"))
      (node (ref "P10") (pin "1") (pinfunction "1_1") (pintype "passive"))
      (node (ref "P11") (pin "1") (pinfunction "1_1") (pintype "passive"))
      (node (ref "P12") (pin "1") (pinfunction "1_1") (pintype "passive"))
      (node (ref "P3") (pin "1") (pinfunction "1_1") (pintype "passive"))
      (node (ref "P4") (pin "2") (pinfunction "2_2") (pintype "passive"))
      (node (ref "P6") (pin "1") (pinfunction "1_1") (pintype "passive"))
      (node (ref "P7") (pin "1") (pinfunction "1_1") (pintype "passive"))
      (node (ref "P8") (pin "1") (pinfunction "1_1") (pintype "passive"))
      (node (ref "P9") (pin "1") (pinfunction "1_1") (pintype "passive"))
      (node (ref "Q1") (pin "2") (pinfunction "S_2") (pintype "passive"))
      (node (ref "Q10") (pin "2") (pinfunction "S_2") (pintype "passive"))
      (node (ref "Q7") (pin "2") (pinfunction "S_2") (pintype "passive"))
      (node (ref "Q9") (pin "2") (pinfunction "S_2") (pintype "passive"))
      (node (ref "R10") (pin "1") (pinfunction "1_1") (pintype "passive"))
      (node (ref "R11") (pin "1") (pinfunction "1_1") (pintype "passive"))
      (node (ref "R12") (pin "1") (pinfunction "1_1") (pintype "passive"))
      (node (ref "R13") (pin "1") (pinfunction "1_1") (pintype "passive"))
      (node (ref "R15") (pin "1") (pinfunction "1_1") (pintype "passive"))
      (node (ref "R22") (pin "1") (pinfunction "1_1") (pintype "passive"))
      (node (ref "R23") (pin "1") (pinfunction "1_1") (pintype "passive"))
      (node (ref "R27") (pin "1") (pinfunction "1_1") (pintype "passive"))
      (node (ref "R3") (pin "1") (pinfunction "1_1") (pintype "passive"))
      (node (ref "R6") (pin "2") (pinfunction "2_2") (pintype "passive"))
      (node (ref "R9") (pin "1") (pinfunction "1_1") (pintype "passive"))
      (node (ref "S1") (pin "3") (pinfunction "3_3") (pintype "passive"))
      (node (ref "S1") (pin "4") (pinfunction "4_4") (pintype "passive"))
      (node (ref "S2") (pin "3") (pinfunction "3_3") (pintype "passive"))
      (node (ref "S2") (pin "4") (pinfunction "4_4") (pintype "passive"))
      (node (ref "U1") (pin "2") (pinfunction "GND_2") (pintype "passive"))
      (node (ref "U14") (pin "3") (pinfunction "VSS_3") (pintype "passive"))
      (node (ref "U15") (pin "3") (pinfunction "VSS_3") (pintype "passive"))
      (node (ref "U18") (pin "1") (pinfunction "GND_1") (pintype "passive"))
      (node (ref "U2") (pin "3") (pinfunction "VSS_3") (pintype "passive"))
      (node (ref "U4") (pin "31") (pinfunction "VSS_31") (pintype "power_in"))
      (node (ref "U4") (pin "45") (pinfunction "VSS_45") (pintype "power_in"))
      (node (ref "U4") (pin "49") (pinfunction "GND_49") (pintype "power_in"))
      (node (ref "U5") (pin "2") (pinfunction "GND_2") (pintype "passive"))
      (node (ref "U6") (pin "1") (pinfunction "CLKIN_1") (pintype "passive"))
      (node (ref "U6") (pin "18") (pinfunction "GND_18") (pintype "passive"))
      (node (ref "U6") (pin "9") (pinfunction "AD0_9") (pintype "passive"))
      (node (ref "U7") (pin "10") (pinfunction "AGND_10") (pintype "passive"))
      (node (ref "U7") (pin "11") (pinfunction "PGND_11") (pintype "passive"))
      (node (ref "U7") (pin "14") (pinfunction "AGND_14") (pintype "passive"))
      (node (ref "U7") (pin "15") (pinfunction "PGND_15") (pintype "passive"))
      (node (ref "U8") (pin "3") (pinfunction "VSS_3") (pintype "passive"))
      (node (ref "Y1") (pin "2") (pinfunction "GND_2") (pintype "passive"))
      (node (ref "Y1") (pin "4") (pinfunction "GND_4") (pintype "passive"))
    )
    (net (code "49") (name "Net-(B1-G)") (class "Default")
      (node (ref "B1") (pin "2") (pinfunction "G_2") (pintype "passive"))
      (node (ref "R14") (pin "2") (pinfunction "2_2") (pintype "passive"))
    )
    (net (code "50") (name "Net-(D3-K)") (class "Default")
      (node (ref "D3") (pin "2") (pinfunction "K_2") (pintype "passive"))
      (node (ref "R25") (pin "2") (pinfunction "2_2") (pintype "passive"))
    )
    (net (code "51") (name "Net-(D4-K)") (class "Default")
      (node (ref "D4") (pin "2") (pinfunction "K_2") (pintype "passive"))
      (node (ref "R26") (pin "2") (pinfunction "2_2") (pintype "passive"))
    )
    (net (code "52") (name "Net-(D5-K)") (class "Default")
      (node (ref "D5") (pin "2") (pinfunction "K_2") (pintype "passive"))
      (node (ref "R17") (pin "2") (pinfunction "2_2") (pintype "passive"))
    )
    (net (code "53") (name "Net-(M1-Pad1)") (class "Default")
      (node (ref "M1") (pin "1") (pinfunction "1_1") (pintype "passive"))
      (node (ref "R7") (pin "2") (pinfunction "2_2") (pintype "passive"))
    )
    (net (code "54") (name "Net-(M2-Pad2)") (class "Default")
      (node (ref "M2") (pin "2") (pinfunction "2_2") (pintype "passive"))
      (node (ref "R8") (pin "2") (pinfunction "2_2") (pintype "passive"))
    )
    (net (code "55") (name "Net-(Q1-D)") (class "Default")
      (node (ref "Q1") (pin "3") (pinfunction "D_3") (pintype "passive"))
      (node (ref "U3") (pin "2") (pinfunction "K_2") (pintype "passive"))
      (node (ref "U9") (pin "2") (pinfunction "K_2") (pintype "passive"))
    )
    (net (code "56") (name "Net-(Q7-D)") (class "Default")
      (node (ref "Q7") (pin "3") (pinfunction "D_3") (pintype "passive"))
      (node (ref "R14") (pin "1") (pinfunction "1_1") (pintype "passive"))
    )
    (net (code "57") (name "Net-(Q10-D)") (class "Default")
      (node (ref "Q10") (pin "3") (pinfunction "D_3") (pintype "passive"))
      (node (ref "R17") (pin "1") (pinfunction "1_1") (pintype "passive"))
    )
    (net (code "58") (name "Net-(R24-Pad1)") (class "Default")
      (node (ref "R24") (pin "1") (pinfunction "1_1") (pintype "passive"))
      (node (ref "S1") (pin "1") (pinfunction "1_1") (pintype "passive"))
    )
    (net (code "59") (name "Net-(U3-A)") (class "Default")
      (node (ref "R2") (pin "2") (pinfunction "2_2") (pintype "passive"))
      (node (ref "U3") (pin "1") (pinfunction "A_1") (pintype "passive"))
    )
    (net (code "60") (name "Net-(U4-ANT)") (class "Default")
      (node (ref "C3") (pin "2") (pinfunction "2_2") (pintype "passive"))
      (node (ref "L1") (pin "1") (pinfunction "1_1") (pintype "passive"))
      (node (ref "U4") (pin "30") (pinfunction "ANT_30") (pintype "bidirectional"))
    )
    (net (code "61") (name "Net-(U5-PROG)") (class "Default")
      (node (ref "R6") (pin "1") (pinfunction "1_1") (pintype "passive"))
      (node (ref "U5") (pin "6") (pinfunction "PROG_6") (pintype "passive"))
    )
    (net (code "62") (name "Net-(U6-CPOUT)") (class "Default")
      (node (ref "C2") (pin "1") (pinfunction "1_1") (pintype "passive"))
      (node (ref "U6") (pin "20") (pinfunction "CPOUT_20") (pintype "passive"))
    )
    (net (code "63") (name "Net-(U6-REGOUT)") (class "Default")
      (node (ref "C12") (pin "2") (pinfunction "2_2") (pintype "passive"))
      (node (ref "U6") (pin "10") (pinfunction "REGOUT_10") (pintype "passive"))
    )
    (net (code "64") (name "Net-(U7-OUTA)") (class "Default")
      (node (ref "R7") (pin "1") (pinfunction "1_1") (pintype "passive"))
      (node (ref "U7") (pin "16") (pinfunction "OUTA_16") (pintype "passive"))
    )
    (net (code "65") (name "Net-(U7-OUTB)") (class "Default")
      (node (ref "M1") (pin "2") (pinfunction "2_2") (pintype "passive"))
      (node (ref "U7") (pin "13") (pinfunction "OUTB_13") (pintype "passive"))
    )
    (net (code "66") (name "Net-(U7-OUTC)") (class "Default")
      (node (ref "M2") (pin "1") (pinfunction "1_1") (pintype "passive"))
      (node (ref "U7") (pin "12") (pinfunction "OUTC_12") (pintype "passive"))
    )
    (net (code "67") (name "Net-(U7-OUTD)") (class "Default")
      (node (ref "R8") (pin "1") (pinfunction "1_1") (pintype "passive"))
      (node (ref "U7") (pin "9") (pinfunction "OUTD_9") (pintype "passive"))
    )
    (net (code "68") (name "Net-(U9-A)") (class "Default")
      (node (ref "R4") (pin "2") (pinfunction "2_2") (pintype "passive"))
      (node (ref "U9") (pin "1") (pinfunction "A_1") (pintype "passive"))
    )
    (net (code "69") (name "unconnected-(J1-CC1-PadA5)") (class "Default")
      (node (ref "J1") (pin "A5") (pinfunction "CC1_A5") (pintype "passive"))
    )
    (net (code "70") (name "unconnected-(J1-CC2-PadB5)") (class "Default")
      (node (ref "J1") (pin "B5") (pinfunction "CC2_B5") (pintype "passive"))
    )
    (net (code "71") (name "unconnected-(J1-D--PadA7)") (class "Default")
      (node (ref "J1") (pin "A7") (pinfunction "D-_A7") (pintype "passive"))
    )
    (net (code "72") (name "unconnected-(J1-NC-PadA2)") (class "Default")
      (node (ref "J1") (pin "A2") (pinfunction "NC_A2") (pintype "passive"))
    )
    (net (code "73") (name "unconnected-(J1-NC-PadA3)") (class "Default")
      (node (ref "J1") (pin "A3") (pinfunction "NC_A3") (pintype "passive"))
    )
    (net (code "74") (name "unconnected-(J1-NC-PadA10)") (class "Default")
      (node (ref "J1") (pin "A10") (pinfunction "NC_A10") (pintype "passive"))
    )
    (net (code "75") (name "unconnected-(J1-NC-PadA11)") (class "Default")
      (node (ref "J1") (pin "A11") (pinfunction "NC_A11") (pintype "passive"))
    )
    (net (code "76") (name "unconnected-(J1-NC-PadB2)") (class "Default")
      (node (ref "J1") (pin "B2") (pinfunction "NC_B2") (pintype "passive"))
    )
    (net (code "77") (name "unconnected-(J1-NC-PadB3)") (class "Default")
      (node (ref "J1") (pin "B3") (pinfunction "NC_B3") (pintype "passive"))
    )
    (net (code "78") (name "unconnected-(J1-NC-PadB10)") (class "Default")
      (node (ref "J1") (pin "B10") (pinfunction "NC_B10") (pintype "passive"))
    )
    (net (code "79") (name "unconnected-(J1-NC-PadB11)") (class "Default")
      (node (ref "J1") (pin "B11") (pinfunction "NC_B11") (pintype "passive"))
    )
    (net (code "80") (name "unconnected-(J1-SBU1-PadA8)") (class "Default")
      (node (ref "J1") (pin "A8") (pinfunction "SBU1_A8") (pintype "passive"))
    )
    (net (code "81") (name "unconnected-(J1-SUB2-PadB8)") (class "Default")
      (node (ref "J1") (pin "B8") (pinfunction "SUB2_B8") (pintype "passive"))
    )
    (net (code "82") (name "unconnected-(U2-DO-Pad2)") (class "Default")
      (node (ref "U2") (pin "2") (pinfunction "DO_2") (pintype "passive"))
    )
    (net (code "83") (name "unconnected-(U4-DCC-Pad47)") (class "Default")
      (node (ref "U4") (pin "47") (pinfunction "DCC_47") (pintype "output"))
    )
    (net (code "84") (name "unconnected-(U4-N.C.-Pad44)") (class "Default")
      (node (ref "U4") (pin "44") (pinfunction "N.C._44") (pintype "power_in+no_connect"))
    )
    (net (code "85") (name "unconnected-(U6-AUX_CL-Pad7)") (class "Default")
      (node (ref "U6") (pin "7") (pinfunction "AUX_CL_7") (pintype "passive"))
    )
    (net (code "86") (name "unconnected-(U6-AUX_DA-Pad6)") (class "Default")
      (node (ref "U6") (pin "6") (pinfunction "AUX_DA_6") (pintype "passive"))
    )
    (net (code "87") (name "unconnected-(U6-FSYNC-Pad11)") (class "Default")
      (node (ref "U6") (pin "11") (pinfunction "FSYNC_11") (pintype "passive"))
    )
    (net (code "88") (name "unconnected-(U6-INT-Pad12)") (class "Default")
      (node (ref "U6") (pin "12") (pinfunction "INT_12") (pintype "passive"))
    )
    (net (code "89") (name "unconnected-(U6-NC-2-Pad2)") (class "Default")
      (node (ref "U6") (pin "2") (pinfunction "NC-2_2") (pintype "passive"))
    )
    (net (code "90") (name "unconnected-(U6-NC-3-Pad3)") (class "Default")
      (node (ref "U6") (pin "3") (pinfunction "NC-3_3") (pintype "passive"))
    )
    (net (code "91") (name "unconnected-(U6-NC-4-Pad4)") (class "Default")
      (node (ref "U6") (pin "4") (pinfunction "NC-4_4") (pintype "passive"))
    )
    (net (code "92") (name "unconnected-(U6-NC-5-Pad5)") (class "Default")
      (node (ref "U6") (pin "5") (pinfunction "NC-5_5") (pintype "passive"))
    )
    (net (code "93") (name "unconnected-(U6-NC-14-Pad14)") (class "Default")
      (node (ref "U6") (pin "14") (pinfunction "NC-14_14") (pintype "passive"))
    )
    (net (code "94") (name "unconnected-(U6-NC-15-Pad15)") (class "Default")
      (node (ref "U6") (pin "15") (pinfunction "NC-15_15") (pintype "passive"))
    )
    (net (code "95") (name "unconnected-(U6-NC-16-Pad16)") (class "Default")
      (node (ref "U6") (pin "16") (pinfunction "NC-16_16") (pintype "passive"))
    )
    (net (code "96") (name "unconnected-(U6-NC-17-Pad17)") (class "Default")
      (node (ref "U6") (pin "17") (pinfunction "NC-17_17") (pintype "passive"))
    )
    (net (code "97") (name "unconnected-(U6-PWR_PAD-Pad25)") (class "Default")
      (node (ref "U6") (pin "25") (pinfunction "PWR_PAD_25") (pintype "passive"))
    )
    (net (code "98") (name "unconnected-(U6-RESV-19-Pad19)") (class "Default")
      (node (ref "U6") (pin "19") (pinfunction "RESV-19_19") (pintype "passive"))
    )
    (net (code "99") (name "unconnected-(U6-RESV-21-Pad21)") (class "Default")
      (node (ref "U6") (pin "21") (pinfunction "RESV-21_21") (pintype "passive"))
    )
    (net (code "100") (name "unconnected-(U6-RESV-22-Pad22)") (class "Default")
      (node (ref "U6") (pin "22") (pinfunction "RESV-22_22") (pintype "passive"))
    )
    (net (code "101") (name "unconnected-(U7-NC-Pad1)") (class "Default")
      (node (ref "U7") (pin "1") (pinfunction "NC_1") (pintype "passive"))
    )
    (net (code "102") (name "unconnected-(U7-NC-Pad5)") (class "Default")
      (node (ref "U7") (pin "5") (pinfunction "NC_5") (pintype "passive"))
    )
    (net (code "103") (name "unconnected-(U8-DO-Pad2)") (class "Default")
      (node (ref "U8") (pin "2") (pinfunction "DO_2") (pintype "passive"))
    )
    (net (code "104") (name "unconnected-(U14-DO-Pad2)") (class "Default")
      (node (ref "U14") (pin "2") (pinfunction "DO_2") (pintype "passive"))
    )
    (net (code "105") (name "unconnected-(U15-DO-Pad2)") (class "Default")
      (node (ref "U15") (pin "2") (pinfunction "DO_2") (pintype "passive"))
    )
  )
)
